# OSO-MISC-22-001_Temperature_GPIO_I2C.net
KiCad netlist of a schematic drawn in EAGLE
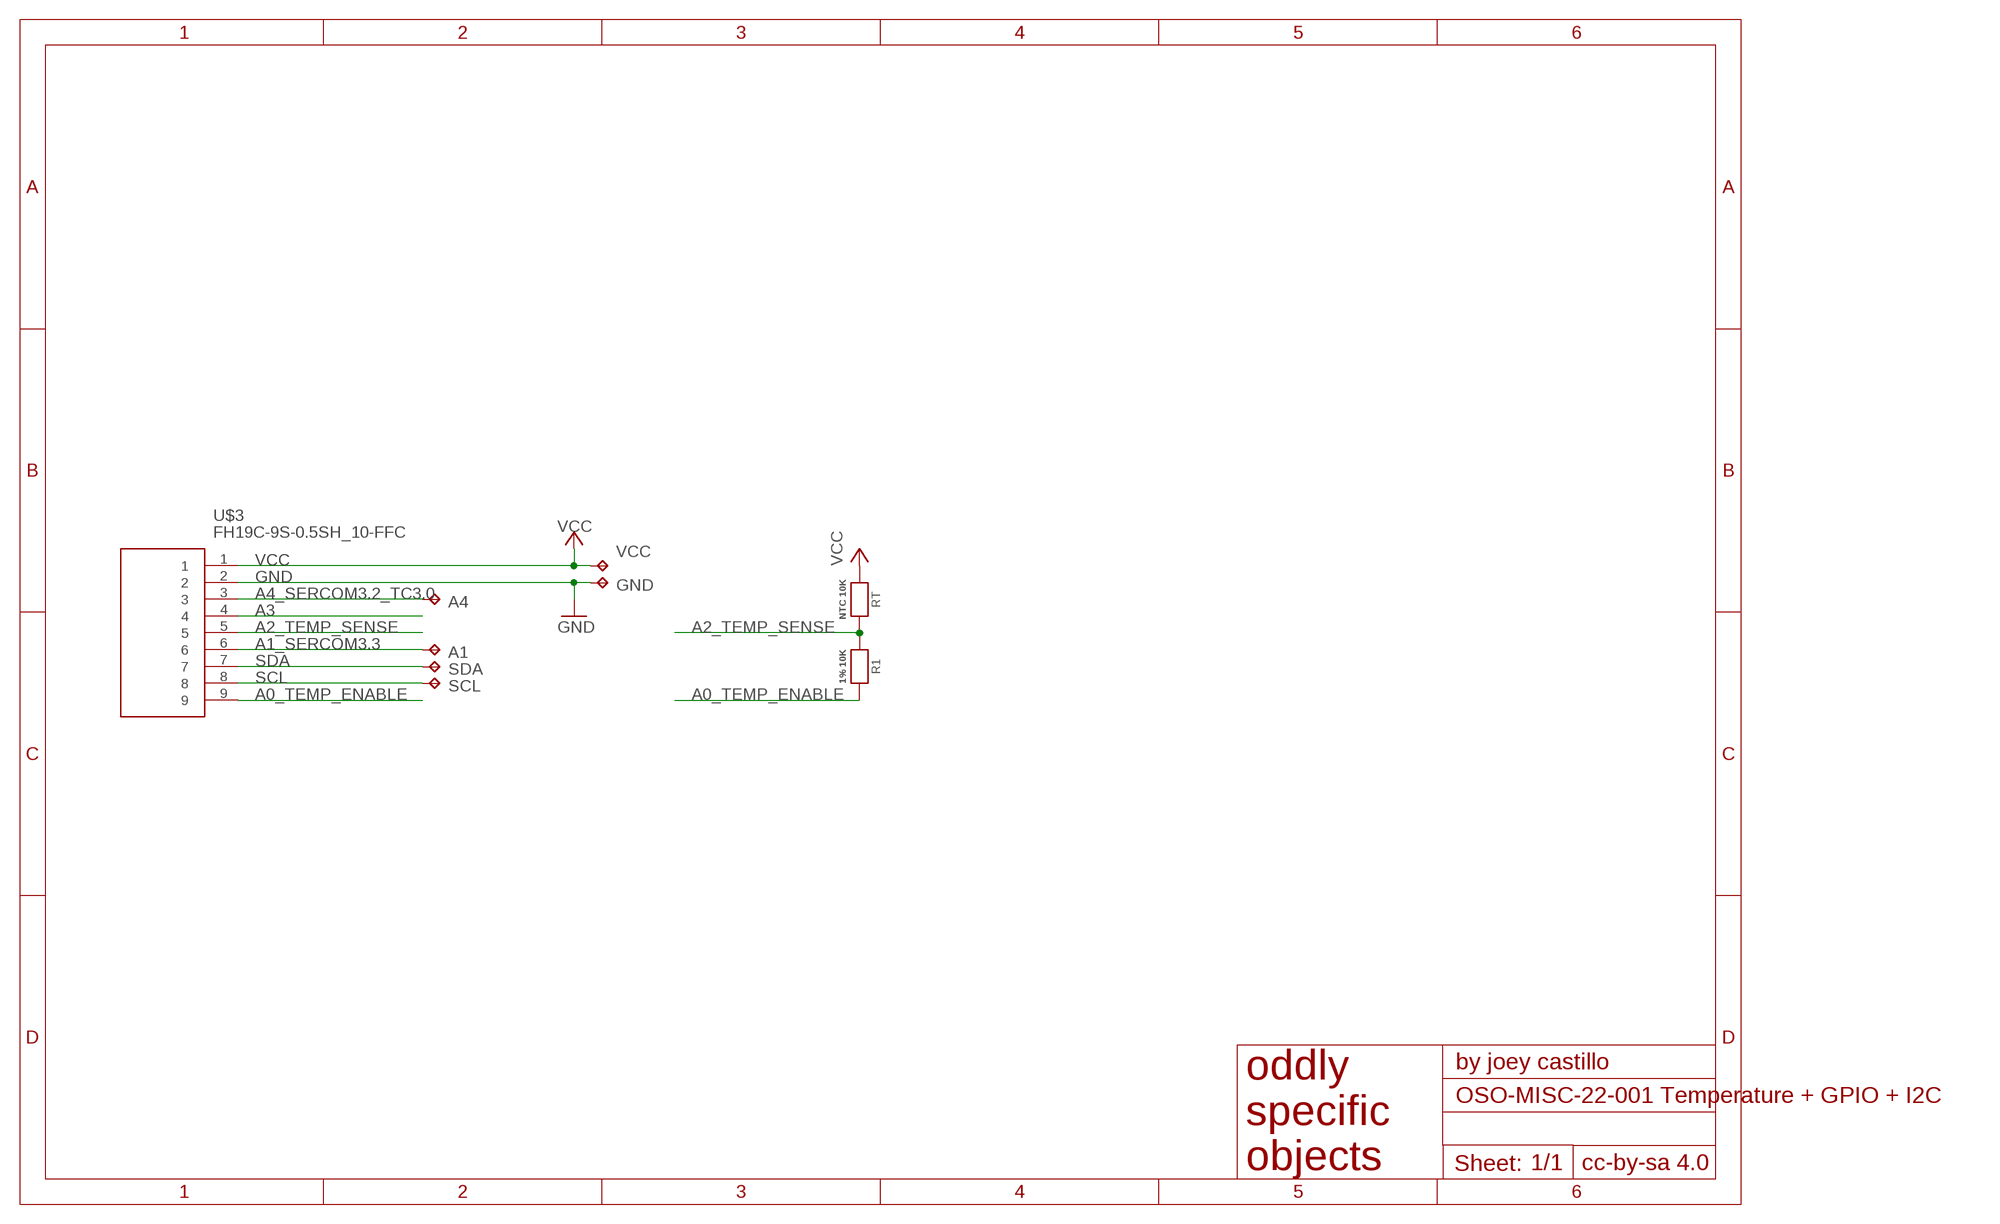
[diagram p0: schematic, sheet 1]

(export (version "E")
  (design (tool "Eeschema 10.0.6"))
  (components
    (comp (ref "A1")
      (value "TPB1,27")
      (footprint "eagle-import:B1,27")
      (libsource (lib "eagle-import") (part "TPB1,27"))
    )
    (comp (ref "A4")
      (value "TPB1,27")
      (footprint "eagle-import:B1,27")
      (libsource (lib "eagle-import") (part "TPB1,27"))
    )
    (comp (ref "GND")
      (value "TPB1,27")
      (footprint "eagle-import:B1,27")
      (libsource (lib "eagle-import") (part "TPB1,27"))
    )
    (comp (ref "R1")
      (value "1% 10K")
      (footprint "eagle-import:_0603MP")
      (libsource (lib "eagle-import") (part "RESISTOR_0603MP"))
    )
    (comp (ref "RT")
      (value "NTC 10K")
      (footprint "eagle-import:_0603MP")
      (libsource (lib "eagle-import") (part "RESISTOR_0603MP"))
    )
    (comp (ref "SCL")
      (value "TPB1,27")
      (footprint "eagle-import:B1,27")
      (libsource (lib "eagle-import") (part "TPB1,27"))
    )
    (comp (ref "SDA")
      (value "TPB1,27")
      (footprint "eagle-import:B1,27")
      (libsource (lib "eagle-import") (part "TPB1,27"))
    )
    (comp (ref "U$3")
      (value "FH19C-9S-0.5SH_10-FFC")
      (footprint "eagle-import:FH19C9S05SH10-FFC")
      (libsource (lib "eagle-import") (part "FH19C-9S-0.5SH_10-FFC"))
    )
    (comp (ref "VCC")
      (value "TPB1,27")
      (footprint "eagle-import:B1,27")
      (libsource (lib "eagle-import") (part "TPB1,27"))
    )
  )
  (nets
    (net (code "1") (name "/A0_TEMP_ENABLE") (class "Default")
      (node (ref "R1") (pin "2") (pinfunction "2_2") (pintype "passive"))
      (node (ref "U$3") (pin "9") (pinfunction "9_9") (pintype "bidirectional"))
    )
    (net (code "2") (name "/A1_SERCOM3.3") (class "Default")
      (node (ref "A1") (pin "TP") (pinfunction "TP_TP") (pintype "input"))
      (node (ref "U$3") (pin "6") (pinfunction "6_6") (pintype "bidirectional"))
    )
    (net (code "3") (name "/A2_TEMP_SENSE") (class "Default")
      (node (ref "R1") (pin "1") (pinfunction "1_1") (pintype "passive"))
      (node (ref "RT") (pin "2") (pinfunction "2_2") (pintype "passive"))
      (node (ref "U$3") (pin "5") (pinfunction "5_5") (pintype "bidirectional"))
    )
    (net (code "4") (name "/A3") (class "Default")
      (node (ref "U$3") (pin "4") (pinfunction "4_4") (pintype "bidirectional"))
    )
    (net (code "5") (name "/A4_SERCOM3.2_TC3.0") (class "Default")
      (node (ref "A4") (pin "TP") (pinfunction "TP_TP") (pintype "input"))
      (node (ref "U$3") (pin "3") (pinfunction "3_3") (pintype "bidirectional"))
    )
    (net (code "6") (name "/SCL") (class "Default")
      (node (ref "SCL") (pin "TP") (pinfunction "TP_TP") (pintype "input"))
      (node (ref "U$3") (pin "8") (pinfunction "8_8") (pintype "bidirectional"))
    )
    (net (code "7") (name "/SDA") (class "Default")
      (node (ref "SDA") (pin "TP") (pinfunction "TP_TP") (pintype "input"))
      (node (ref "U$3") (pin "7") (pinfunction "7_7") (pintype "bidirectional"))
    )
    (net (code "8") (name "GND") (class "Default")
      (node (ref "GND") (pin "TP") (pinfunction "TP_TP") (pintype "input"))
      (node (ref "U$3") (pin "2") (pinfunction "2_2") (pintype "bidirectional"))
    )
    (net (code "9") (name "VCC") (class "Default")
      (node (ref "RT") (pin "1") (pinfunction "1_1") (pintype "passive"))
      (node (ref "U$3") (pin "1") (pinfunction "1_1") (pintype "bidirectional"))
      (node (ref "VCC") (pin "TP") (pinfunction "TP_TP") (pintype "input"))
    )
  )
)
